# lazurite_ble_cs75_l2_3.net
KiCad netlist of a schematic drawn in EAGLE
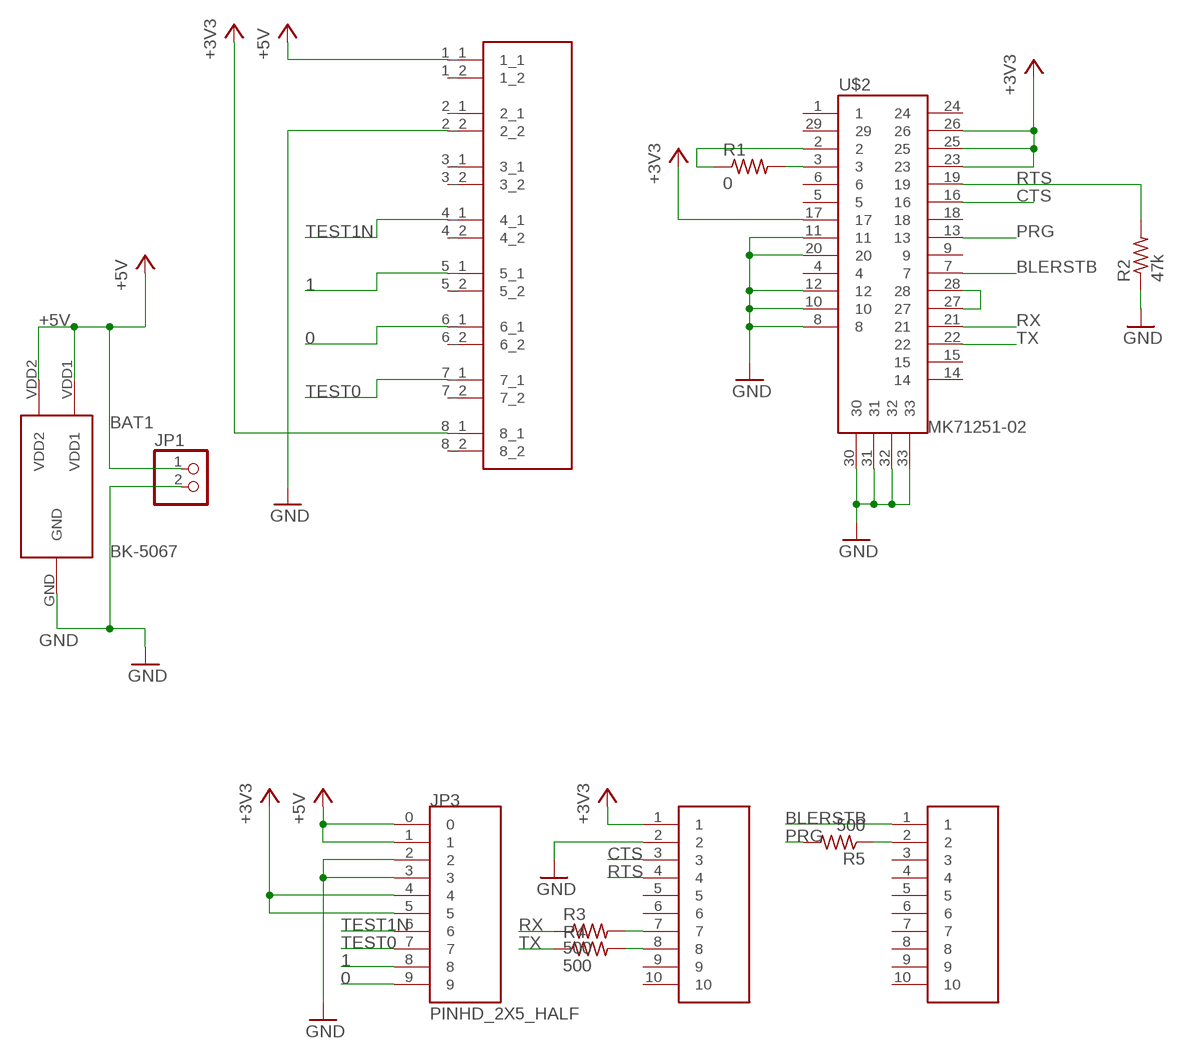
[diagram p0: schematic, sheet 1]

(export (version "E")
  (design (tool "Eeschema 10.0.6"))
  (components
    (comp (ref "BAT1")
      (value "BK-5067")
      (footprint "eagle-import:BK-5067")
      (libsource (lib "eagle-import") (part "BK-5067"))
    )
    (comp (ref "JP1")
      (value "PINHD-1X2")
      (footprint "eagle-import:1X02")
      (libsource (lib "eagle-import") (part "PINHD-1X2"))
    )
    (comp (ref "JP3")
      (value "PINHD_2X5_HALF")
      (footprint "eagle-import:PINHD_2X5_HALF")
      (libsource (lib "eagle-import") (part "PINHD_2X5_HALF"))
    )
    (comp (ref "R1")
      (value "0")
      (footprint "eagle-import:R0402")
      (libsource (lib "eagle-import") (part "R-US_R0402"))
    )
    (comp (ref "R2")
      (value "47k")
      (footprint "eagle-import:R0402")
      (libsource (lib "eagle-import") (part "R-US_R0402"))
    )
    (comp (ref "R3")
      (value "500")
      (footprint "eagle-import:R0402")
      (libsource (lib "eagle-import") (part "R-US_R0402"))
    )
    (comp (ref "R4")
      (value "500")
      (footprint "eagle-import:R0402")
      (libsource (lib "eagle-import") (part "R-US_R0402"))
    )
    (comp (ref "R5")
      (value "500")
      (footprint "eagle-import:R0402")
      (libsource (lib "eagle-import") (part "R-US_R0402"))
    )
    (comp (ref "U$1")
      (value "XB-1-X")
      (footprint "eagle-import:XB-1-X")
      (libsource (lib "eagle-import") (part "XB-1-X"))
    )
    (comp (ref "U$2")
      (value "MK71251-02")
      (footprint "eagle-import:MK71251-02")
      (libsource (lib "eagle-import") (part "MK71251-02"))
    )
    (comp (ref "U$3")
      (value "PINHD_1_10_HALF")
      (footprint "eagle-import:PINHD_1X10_HALF")
      (libsource (lib "eagle-import") (part "PINHD_1_10_HALF"))
    )
    (comp (ref "U$4")
      (value "PINHD_1_10_HALF")
      (footprint "eagle-import:PINHD_1X10_HALF")
      (libsource (lib "eagle-import") (part "PINHD_1_10_HALF"))
    )
  )
  (nets
    (net (code "1") (name "+3V3") (class "Default")
      (node (ref "JP3") (pin "4") (pinfunction "4_4") (pintype "bidirectional"))
      (node (ref "JP3") (pin "5") (pinfunction "5_5") (pintype "bidirectional"))
      (node (ref "U$1") (pin "8_1") (pinfunction "8_1_8_1") (pintype "bidirectional"))
      (node (ref "U$2") (pin "17") (pinfunction "17_17") (pintype "power_in"))
      (node (ref "U$2") (pin "23") (pinfunction "23_23") (pintype "bidirectional"))
      (node (ref "U$2") (pin "25") (pinfunction "25_25") (pintype "bidirectional"))
      (node (ref "U$2") (pin "26") (pinfunction "26_26") (pintype "bidirectional"))
      (node (ref "U$3") (pin "1") (pinfunction "1_1") (pintype "bidirectional"))
    )
    (net (code "2") (name "+5V") (class "Default")
      (node (ref "BAT1") (pin "VDD1") (pinfunction "VDD1_VDD1") (pintype "power_in"))
      (node (ref "BAT1") (pin "VDD2") (pinfunction "VDD2_VDD2") (pintype "power_in"))
      (node (ref "JP1") (pin "1") (pinfunction "1_1") (pintype "passive"))
      (node (ref "JP3") (pin "0") (pinfunction "0_0") (pintype "bidirectional"))
      (node (ref "JP3") (pin "1") (pinfunction "1_1") (pintype "bidirectional"))
      (node (ref "U$1") (pin "1_1") (pinfunction "1_1_1_1") (pintype "bidirectional"))
    )
    (net (code "3") (name "/0") (class "Default")
      (node (ref "JP3") (pin "9") (pinfunction "9_9") (pintype "bidirectional"))
      (node (ref "U$1") (pin "6_1") (pinfunction "6_1_6_1") (pintype "bidirectional"))
    )
    (net (code "4") (name "/1") (class "Default")
      (node (ref "JP3") (pin "8") (pinfunction "8_8") (pintype "bidirectional"))
      (node (ref "U$1") (pin "5_1") (pinfunction "5_1_5_1") (pintype "bidirectional"))
    )
    (net (code "5") (name "/BLERSTB") (class "Default")
      (node (ref "U$2") (pin "7") (pinfunction "7_7") (pintype "input"))
      (node (ref "U$4") (pin "1") (pinfunction "1_1") (pintype "bidirectional"))
    )
    (net (code "6") (name "/CTS") (class "Default")
      (node (ref "U$2") (pin "16") (pinfunction "16_16") (pintype "bidirectional"))
      (node (ref "U$3") (pin "3") (pinfunction "3_3") (pintype "bidirectional"))
    )
    (net (code "7") (name "/PRG") (class "Default")
      (node (ref "R5") (pin "2") (pinfunction "2_2") (pintype "passive"))
      (node (ref "U$2") (pin "13") (pinfunction "13_13") (pintype "bidirectional"))
    )
    (net (code "8") (name "/RTS") (class "Default")
      (node (ref "R2") (pin "2") (pinfunction "2_2") (pintype "passive"))
      (node (ref "U$2") (pin "19") (pinfunction "19_19") (pintype "input"))
      (node (ref "U$3") (pin "4") (pinfunction "4_4") (pintype "bidirectional"))
    )
    (net (code "9") (name "/RX") (class "Default")
      (node (ref "R3") (pin "1") (pinfunction "1_1") (pintype "passive"))
      (node (ref "U$2") (pin "21") (pinfunction "21_21") (pintype "bidirectional"))
    )
    (net (code "10") (name "/TEST0") (class "Default")
      (node (ref "JP3") (pin "7") (pinfunction "7_7") (pintype "bidirectional"))
      (node (ref "U$1") (pin "7_1") (pinfunction "7_1_7_1") (pintype "bidirectional"))
    )
    (net (code "11") (name "/TEST1N") (class "Default")
      (node (ref "JP3") (pin "6") (pinfunction "6_6") (pintype "bidirectional"))
      (node (ref "U$1") (pin "4_1") (pinfunction "4_1_4_1") (pintype "bidirectional"))
    )
    (net (code "12") (name "/TX") (class "Default")
      (node (ref "R4") (pin "1") (pinfunction "1_1") (pintype "passive"))
      (node (ref "U$2") (pin "22") (pinfunction "22_22") (pintype "bidirectional"))
    )
    (net (code "13") (name "GND") (class "Default")
      (node (ref "BAT1") (pin "GND") (pinfunction "GND_GND") (pintype "power_in"))
      (node (ref "JP1") (pin "2") (pinfunction "2_2") (pintype "passive"))
      (node (ref "JP3") (pin "2") (pinfunction "2_2") (pintype "bidirectional"))
      (node (ref "JP3") (pin "3") (pinfunction "3_3") (pintype "bidirectional"))
      (node (ref "R2") (pin "1") (pinfunction "1_1") (pintype "passive"))
      (node (ref "U$1") (pin "2_2") (pinfunction "2_2_2_2") (pintype "bidirectional"))
      (node (ref "U$2") (pin "10") (pinfunction "10_10") (pintype "input"))
      (node (ref "U$2") (pin "11") (pinfunction "11_11") (pintype "bidirectional"))
      (node (ref "U$2") (pin "12") (pinfunction "12_12") (pintype "input"))
      (node (ref "U$2") (pin "20") (pinfunction "20_20") (pintype "bidirectional"))
      (node (ref "U$2") (pin "30") (pinfunction "30_30") (pintype "power_in"))
      (node (ref "U$2") (pin "31") (pinfunction "31_31") (pintype "power_in"))
      (node (ref "U$2") (pin "32") (pinfunction "32_32") (pintype "power_in"))
      (node (ref "U$2") (pin "33") (pinfunction "33_33") (pintype "power_in"))
      (node (ref "U$2") (pin "8") (pinfunction "8_8") (pintype "input"))
      (node (ref "U$3") (pin "2") (pinfunction "2_2") (pintype "bidirectional"))
    )
    (net (code "14") (name "Net-(R1-Pad1)") (class "Default")
      (node (ref "R1") (pin "1") (pinfunction "1_1") (pintype "passive"))
      (node (ref "U$2") (pin "2") (pinfunction "2_2") (pintype "input"))
    )
    (net (code "15") (name "Net-(R1-Pad2)") (class "Default")
      (node (ref "R1") (pin "2") (pinfunction "2_2") (pintype "passive"))
      (node (ref "U$2") (pin "3") (pinfunction "3_3") (pintype "bidirectional"))
    )
    (net (code "16") (name "Net-(R3-Pad2)") (class "Default")
      (node (ref "R3") (pin "2") (pinfunction "2_2") (pintype "passive"))
      (node (ref "U$3") (pin "7") (pinfunction "7_7") (pintype "bidirectional"))
    )
    (net (code "17") (name "Net-(R4-Pad2)") (class "Default")
      (node (ref "R4") (pin "2") (pinfunction "2_2") (pintype "passive"))
      (node (ref "U$3") (pin "8") (pinfunction "8_8") (pintype "bidirectional"))
    )
    (net (code "18") (name "Net-(R5-Pad1)") (class "Default")
      (node (ref "R5") (pin "1") (pinfunction "1_1") (pintype "passive"))
      (node (ref "U$4") (pin "2") (pinfunction "2_2") (pintype "bidirectional"))
    )
    (net (code "19") (name "Net-(U$2-Pad27)") (class "Default")
      (node (ref "U$2") (pin "27") (pinfunction "27_27") (pintype "bidirectional"))
      (node (ref "U$2") (pin "28") (pinfunction "28_28") (pintype "bidirectional"))
    )
    (net (code "20") (name "unconnected-(U$1-Pad1_2)") (class "Default")
      (node (ref "U$1") (pin "1_2") (pinfunction "1_2_1_2") (pintype "bidirectional"))
    )
    (net (code "21") (name "unconnected-(U$1-Pad2_1)") (class "Default")
      (node (ref "U$1") (pin "2_1") (pinfunction "2_1_2_1") (pintype "bidirectional"))
    )
    (net (code "22") (name "unconnected-(U$1-Pad3_1)") (class "Default")
      (node (ref "U$1") (pin "3_1") (pinfunction "3_1_3_1") (pintype "bidirectional"))
    )
    (net (code "23") (name "unconnected-(U$1-Pad3_2)") (class "Default")
      (node (ref "U$1") (pin "3_2") (pinfunction "3_2_3_2") (pintype "bidirectional"))
    )
    (net (code "24") (name "unconnected-(U$1-Pad4_2)") (class "Default")
      (node (ref "U$1") (pin "4_2") (pinfunction "4_2_4_2") (pintype "bidirectional"))
    )
    (net (code "25") (name "unconnected-(U$1-Pad5_2)") (class "Default")
      (node (ref "U$1") (pin "5_2") (pinfunction "5_2_5_2") (pintype "bidirectional"))
    )
    (net (code "26") (name "unconnected-(U$1-Pad6_2)") (class "Default")
      (node (ref "U$1") (pin "6_2") (pinfunction "6_2_6_2") (pintype "bidirectional"))
    )
    (net (code "27") (name "unconnected-(U$1-Pad7_2)") (class "Default")
      (node (ref "U$1") (pin "7_2") (pinfunction "7_2_7_2") (pintype "bidirectional"))
    )
    (net (code "28") (name "unconnected-(U$1-Pad8_2)") (class "Default")
      (node (ref "U$1") (pin "8_2") (pinfunction "8_2_8_2") (pintype "bidirectional"))
    )
    (net (code "29") (name "unconnected-(U$2-Pad1)") (class "Default")
      (node (ref "U$2") (pin "1") (pinfunction "1_1") (pintype "no_connect"))
    )
    (net (code "30") (name "unconnected-(U$2-Pad4)") (class "Default")
      (node (ref "U$2") (pin "4") (pinfunction "4_4") (pintype "bidirectional"))
    )
    (net (code "31") (name "unconnected-(U$2-Pad5)") (class "Default")
      (node (ref "U$2") (pin "5") (pinfunction "5_5") (pintype "bidirectional"))
    )
    (net (code "32") (name "unconnected-(U$2-Pad6)") (class "Default")
      (node (ref "U$2") (pin "6") (pinfunction "6_6") (pintype "bidirectional"))
    )
    (net (code "33") (name "unconnected-(U$2-Pad9)") (class "Default")
      (node (ref "U$2") (pin "9") (pinfunction "9_9") (pintype "bidirectional"))
    )
    (net (code "34") (name "unconnected-(U$2-Pad14)") (class "Default")
      (node (ref "U$2") (pin "14") (pinfunction "14_14") (pintype "bidirectional"))
    )
    (net (code "35") (name "unconnected-(U$2-Pad15)") (class "Default")
      (node (ref "U$2") (pin "15") (pinfunction "15_15") (pintype "bidirectional"))
    )
    (net (code "36") (name "unconnected-(U$2-Pad18)") (class "Default")
      (node (ref "U$2") (pin "18") (pinfunction "18_18") (pintype "bidirectional"))
    )
    (net (code "37") (name "unconnected-(U$2-Pad24)") (class "Default")
      (node (ref "U$2") (pin "24") (pinfunction "24_24") (pintype "bidirectional"))
    )
    (net (code "38") (name "unconnected-(U$2-Pad29)") (class "Default")
      (node (ref "U$2") (pin "29") (pinfunction "29_29") (pintype "no_connect"))
    )
    (net (code "39") (name "unconnected-(U$3-Pad5)") (class "Default")
      (node (ref "U$3") (pin "5") (pinfunction "5_5") (pintype "bidirectional"))
    )
    (net (code "40") (name "unconnected-(U$3-Pad6)") (class "Default")
      (node (ref "U$3") (pin "6") (pinfunction "6_6") (pintype "bidirectional"))
    )
    (net (code "41") (name "unconnected-(U$3-Pad9)") (class "Default")
      (node (ref "U$3") (pin "9") (pinfunction "9_9") (pintype "bidirectional"))
    )
    (net (code "42") (name "unconnected-(U$3-Pad10)") (class "Default")
      (node (ref "U$3") (pin "10") (pinfunction "10_10") (pintype "bidirectional"))
    )
    (net (code "43") (name "unconnected-(U$4-Pad3)") (class "Default")
      (node (ref "U$4") (pin "3") (pinfunction "3_3") (pintype "bidirectional"))
    )
    (net (code "44") (name "unconnected-(U$4-Pad4)") (class "Default")
      (node (ref "U$4") (pin "4") (pinfunction "4_4") (pintype "bidirectional"))
    )
    (net (code "45") (name "unconnected-(U$4-Pad5)") (class "Default")
      (node (ref "U$4") (pin "5") (pinfunction "5_5") (pintype "bidirectional"))
    )
    (net (code "46") (name "unconnected-(U$4-Pad6)") (class "Default")
      (node (ref "U$4") (pin "6") (pinfunction "6_6") (pintype "bidirectional"))
    )
    (net (code "47") (name "unconnected-(U$4-Pad7)") (class "Default")
      (node (ref "U$4") (pin "7") (pinfunction "7_7") (pintype "bidirectional"))
    )
    (net (code "48") (name "unconnected-(U$4-Pad8)") (class "Default")
      (node (ref "U$4") (pin "8") (pinfunction "8_8") (pintype "bidirectional"))
    )
    (net (code "49") (name "unconnected-(U$4-Pad9)") (class "Default")
      (node (ref "U$4") (pin "9") (pinfunction "9_9") (pintype "bidirectional"))
    )
    (net (code "50") (name "unconnected-(U$4-Pad10)") (class "Default")
      (node (ref "U$4") (pin "10") (pinfunction "10_10") (pintype "bidirectional"))
    )
  )
)
